# Reflective_Sensors.net
KiCad netlist of a schematic drawn in Altium Designer
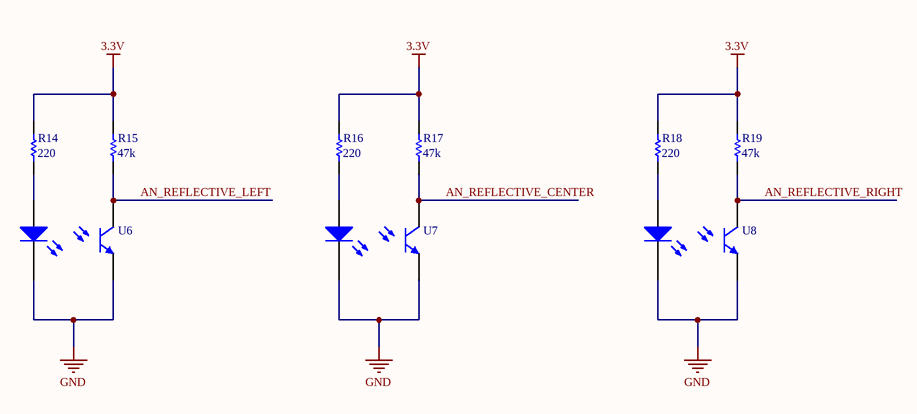
[diagram p0: Reflective_Sensors.SchDoc]

(export (version "E")
  (design (tool "Eeschema 10.0.6"))
  (components
    (comp (ref "R14")
      (value "220")
      (footprint "0805")
      (description "Resistor")
      (fields (field (name "PUBLISHER") "Altium Limited"))
      (libsource (lib "passives") (part "Resistor"))
    )
    (comp (ref "R15")
      (value "47k")
      (footprint "0805")
      (description "Resistor")
      (fields (field (name "PUBLISHER") "Altium Limited"))
      (libsource (lib "passives") (part "Resistor"))
    )
    (comp (ref "R16")
      (value "220")
      (footprint "0805")
      (description "Resistor")
      (fields (field (name "PUBLISHER") "Altium Limited"))
      (libsource (lib "passives") (part "Resistor"))
    )
    (comp (ref "R17")
      (value "47k")
      (footprint "0805")
      (description "Resistor")
      (fields (field (name "PUBLISHER") "Altium Limited"))
      (libsource (lib "passives") (part "Resistor"))
    )
    (comp (ref "R18")
      (value "220")
      (footprint "0805")
      (description "Resistor")
      (fields (field (name "PUBLISHER") "Altium Limited"))
      (libsource (lib "passives") (part "Resistor"))
    )
    (comp (ref "R19")
      (value "47k")
      (footprint "0805")
      (description "Resistor")
      (fields (field (name "PUBLISHER") "Altium Limited"))
      (libsource (lib "passives") (part "Resistor"))
    )
    (comp (ref "U6")
      (value "QRE1113GR")
      (footprint "QRE1113GR")
      (libsource (lib "Devices") (part "QRE1113GR"))
    )
    (comp (ref "U7")
      (value "QRE1113GR")
      (footprint "QRE1113GR")
      (libsource (lib "Devices") (part "QRE1113GR"))
    )
    (comp (ref "U8")
      (value "QRE1113GR")
      (footprint "QRE1113GR")
      (libsource (lib "Devices") (part "QRE1113GR"))
    )
  )
  (nets
    (net (code "1") (name "/AN_REFLECTIVE_CENTER") (class "Default")
      (node (ref "R17") (pin "1") (pinfunction "1_1") (pintype "passive"))
      (node (ref "U7") (pin "3") (pinfunction "COLLECTOR_3") (pintype "passive"))
    )
    (net (code "2") (name "/AN_REFLECTIVE_LEFT") (class "Default")
      (node (ref "R15") (pin "1") (pinfunction "1_1") (pintype "passive"))
      (node (ref "U6") (pin "3") (pinfunction "COLLECTOR_3") (pintype "passive"))
    )
    (net (code "3") (name "/AN_REFLECTIVE_RIGHT") (class "Default")
      (node (ref "R19") (pin "1") (pinfunction "1_1") (pintype "passive"))
      (node (ref "U8") (pin "3") (pinfunction "COLLECTOR_3") (pintype "passive"))
    )
    (net (code "4") (name "3.3V") (class "Default")
      (node (ref "R14") (pin "2") (pinfunction "2_2") (pintype "passive"))
      (node (ref "R15") (pin "2") (pinfunction "2_2") (pintype "passive"))
      (node (ref "R16") (pin "2") (pinfunction "2_2") (pintype "passive"))
      (node (ref "R17") (pin "2") (pinfunction "2_2") (pintype "passive"))
      (node (ref "R18") (pin "2") (pinfunction "2_2") (pintype "passive"))
      (node (ref "R19") (pin "2") (pinfunction "2_2") (pintype "passive"))
    )
    (net (code "5") (name "GND") (class "Default")
      (node (ref "U6") (pin "2") (pinfunction "CATHODE_2") (pintype "passive"))
      (node (ref "U6") (pin "4") (pinfunction "EMITTER_4") (pintype "passive"))
      (node (ref "U7") (pin "2") (pinfunction "CATHODE_2") (pintype "passive"))
      (node (ref "U7") (pin "4") (pinfunction "EMITTER_4") (pintype "passive"))
      (node (ref "U8") (pin "2") (pinfunction "CATHODE_2") (pintype "passive"))
      (node (ref "U8") (pin "4") (pinfunction "EMITTER_4") (pintype "passive"))
    )
    (net (code "6") (name "Net-(U6-ANODE)") (class "Default")
      (node (ref "R14") (pin "1") (pinfunction "1_1") (pintype "passive"))
      (node (ref "U6") (pin "1") (pinfunction "ANODE_1") (pintype "passive"))
    )
    (net (code "7") (name "Net-(U7-ANODE)") (class "Default")
      (node (ref "R16") (pin "1") (pinfunction "1_1") (pintype "passive"))
      (node (ref "U7") (pin "1") (pinfunction "ANODE_1") (pintype "passive"))
    )
    (net (code "8") (name "Net-(U8-ANODE)") (class "Default")
      (node (ref "R18") (pin "1") (pinfunction "1_1") (pintype "passive"))
      (node (ref "U8") (pin "1") (pinfunction "ANODE_1") (pintype "passive"))
    )
  )
)
